# Mechanical.net
KiCad netlist of a schematic drawn in Altium Designer
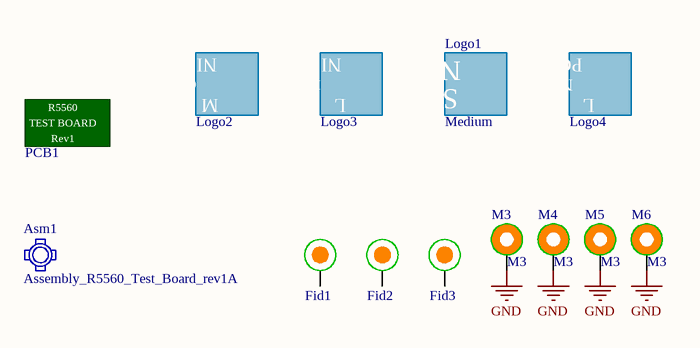
[diagram p0: Mechanical.SchDoc]

(export (version "E")
  (design (tool "Eeschema 10.0.6"))
  (components
    (comp (ref "Asm1")
      (value "Assembly_R5560_Test_Board_rev1A")
      (libsource (lib "Assembly_Jobs__SARAversion-62") (part "Assembly_R5560_Test_Board_rev1A"))
    )
    (comp (ref "Fid1")
      (value "PCB_Fiducial_Round_1mm")
      (footprint "PCB_Fiducial_Round_1mm")
      (libsource (lib "PCB Mech__SARAversion-70") (part "PCB_Fiducial_Round_1mm"))
    )
    (comp (ref "Fid2")
      (value "PCB_Fiducial_Round_1mm")
      (footprint "PCB_Fiducial_Round_1mm")
      (libsource (lib "PCB Mech__SARAversion-70") (part "PCB_Fiducial_Round_1mm"))
    )
    (comp (ref "Fid3")
      (value "PCB_Fiducial_Round_1mm")
      (footprint "PCB_Fiducial_Round_1mm")
      (libsource (lib "PCB Mech__SARAversion-70") (part "PCB_Fiducial_Round_1mm"))
    )
    (comp (ref "Logo1")
      (value "Medium")
      (footprint "NI_SN_MEDIUM")
      (description "NI_SN_MEDIUM")
      (libsource (lib "Logos__SARAversion-7") (part "NI_SN_MEDIUM"))
    )
    (comp (ref "Logo2")
      (value "NI_COMPLETE_M_LOGO")
      (footprint "NI_COMPLETE_M_LOGO")
      (libsource (lib "Logos__SARAversion-7") (part "NI_COMPLETE_M_LOGO"))
    )
    (comp (ref "Logo3")
      (value "~")
      (footprint "NI_ProjectName_L_Serigraphy")
      (description "NI_ProjectName_L_Serigraphy")
      (libsource (lib "Logos__SARAversion-7") (part "NI_ProjectName_L_Serigraphy"))
    )
    (comp (ref "Logo4")
      (value "PCB_Number_L")
      (footprint "NI_PCB_Number_L_Serigraphy")
      (description "NI_PCB_Number_L_Serigraphy")
      (libsource (lib "Logos__SARAversion-8") (part "NI_PCB_Number_L_Serigraphy"))
    )
    (comp (ref "M3")
      (value "M3")
      (footprint "PCBPad_M3_Head6mm")
      (libsource (lib "PCB Mech__SARAversion-70") (part "PCBPad_M3_Head6mm"))
    )
    (comp (ref "M4")
      (value "M3")
      (footprint "PCBPad_M3_Head6mm")
      (libsource (lib "PCB Mech__SARAversion-70") (part "PCBPad_M3_Head6mm"))
    )
    (comp (ref "M5")
      (value "M3")
      (footprint "PCBPad_M3_Head6mm")
      (libsource (lib "PCB Mech__SARAversion-70") (part "PCBPad_M3_Head6mm"))
    )
    (comp (ref "M6")
      (value "M3")
      (footprint "PCBPad_M3_Head6mm")
      (libsource (lib "PCB Mech__SARAversion-70") (part "PCBPad_M3_Head6mm"))
    )
    (comp (ref "PCB1")
      (value "PCB_R5560_Test_Board_rev1")
      (libsource (lib "PCBs__SARAversion-62") (part "PCB_R5560_Test_Board_rev1"))
    )
  )
  (nets
    (net (code "1") (name "GND") (class "Default")
      (node (ref "M3") (pin "1") (pinfunction "1_1") (pintype "passive"))
      (node (ref "M4") (pin "1") (pinfunction "1_1") (pintype "passive"))
      (node (ref "M5") (pin "1") (pinfunction "1_1") (pintype "passive"))
      (node (ref "M6") (pin "1") (pinfunction "1_1") (pintype "passive"))
    )
    (net (code "2") (name "unconnected-(Fid1-Pad1)") (class "Default")
      (node (ref "Fid1") (pin "1") (pinfunction "1_1") (pintype "passive"))
    )
    (net (code "3") (name "unconnected-(Fid2-Pad1)") (class "Default")
      (node (ref "Fid2") (pin "1") (pinfunction "1_1") (pintype "passive"))
    )
    (net (code "4") (name "unconnected-(Fid3-Pad1)") (class "Default")
      (node (ref "Fid3") (pin "1") (pinfunction "1_1") (pintype "passive"))
    )
  )
)
